# sensor_v6_no_gnd.net
KiCad netlist of a schematic drawn in EAGLE
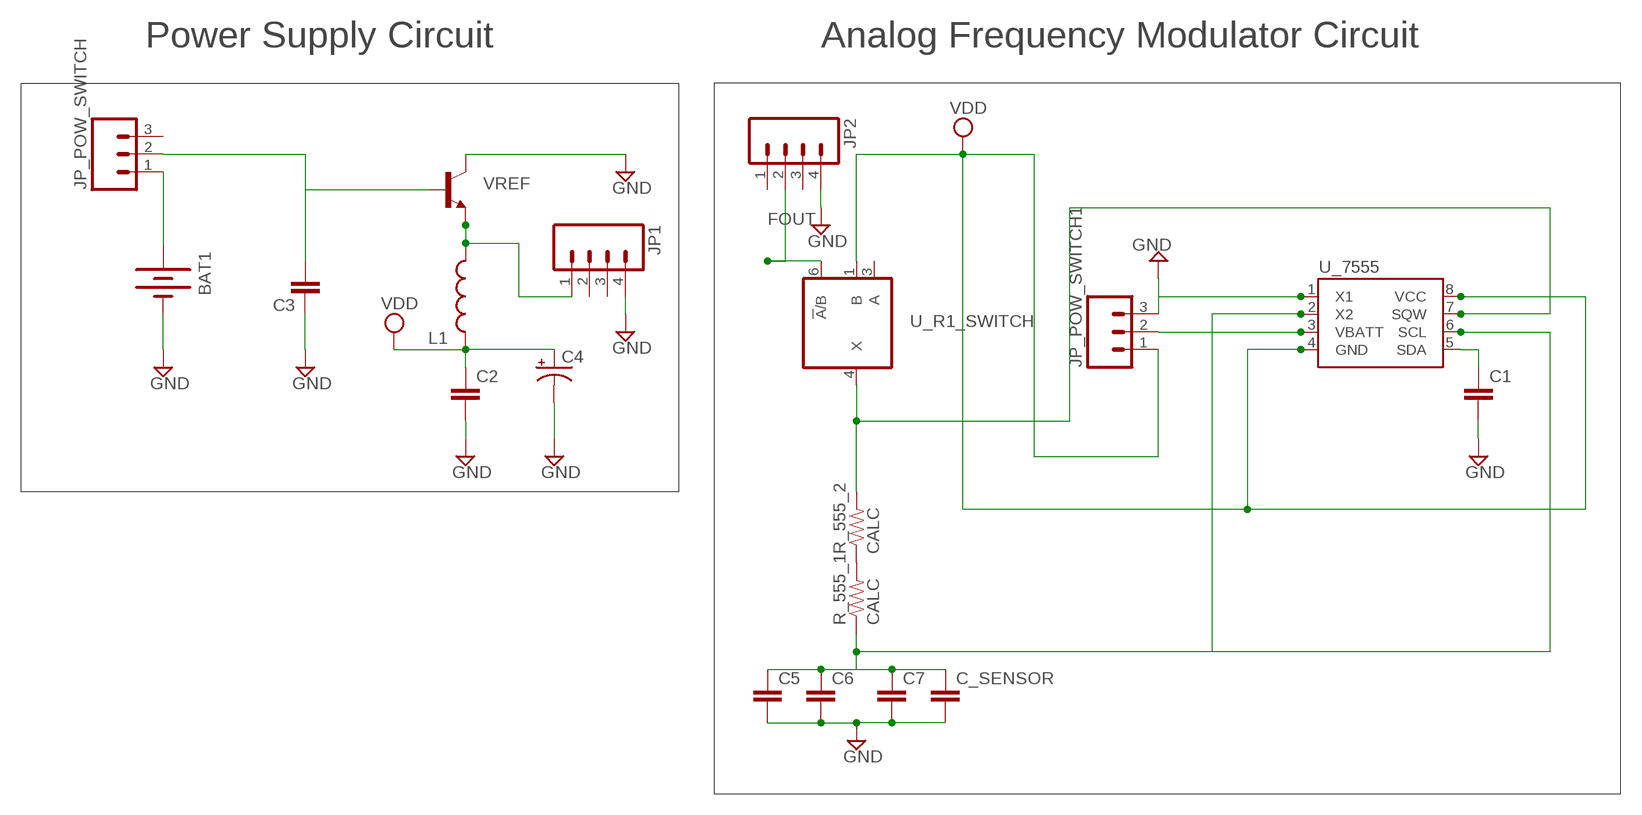
[diagram p0: schematic, sheet 1]

(export (version "E")
  (design (tool "Eeschema 10.0.6"))
  (components
    (comp (ref "BAT1")
      (value "BATTERY20PTH_LAB")
      (footprint "eagle-import:BATTCOM_20MM_PTH")
      (libsource (lib "eagle-import") (part "BATTERY20PTH_LAB"))
    )
    (comp (ref "C1")
      (value "CAP0603-CAP")
      (footprint "eagle-import:0603-CAP")
      (libsource (lib "eagle-import") (part "SparkFun-Capacitors_CAP0603-CAP"))
    )
    (comp (ref "C2")
      (value "CAP0603-CAP")
      (footprint "eagle-import:0603-CAP")
      (libsource (lib "eagle-import") (part "SparkFun-Capacitors_CAP0603-CAP"))
    )
    (comp (ref "C3")
      (value "CAP0603-CAP")
      (footprint "eagle-import:0603-CAP")
      (libsource (lib "eagle-import") (part "SparkFun-Capacitors_CAP0603-CAP"))
    )
    (comp (ref "C4")
      (value "CAP_POL1206")
      (footprint "eagle-import:EIA3216")
      (libsource (lib "eagle-import") (part "CAP_POL1206"))
    )
    (comp (ref "C5")
      (value "CAP0805")
      (footprint "eagle-import:0805")
      (libsource (lib "eagle-import") (part "CAP0805"))
    )
    (comp (ref "C6")
      (value "CAP0805")
      (footprint "eagle-import:0805")
      (libsource (lib "eagle-import") (part "CAP0805"))
    )
    (comp (ref "C7")
      (value "CAP0805")
      (footprint "eagle-import:0805")
      (libsource (lib "eagle-import") (part "CAP0805"))
    )
    (comp (ref "C_SENSOR")
      (value "CAP0805")
      (footprint "eagle-import:0805")
      (libsource (lib "eagle-import") (part "CAP0805"))
    )
    (comp (ref "JP1")
      (value "M04LOCK")
      (footprint "eagle-import:1X04_LOCK")
      (libsource (lib "eagle-import") (part "M04LOCK"))
    )
    (comp (ref "JP2")
      (value "M04LOCK")
      (footprint "eagle-import:1X04_LOCK")
      (libsource (lib "eagle-import") (part "M04LOCK"))
    )
    (comp (ref "JP_POW_SWITCH")
      (value "M03LOCK")
      (footprint "eagle-import:1X03_LOCK")
      (libsource (lib "eagle-import") (part "M03LOCK"))
    )
    (comp (ref "JP_POW_SWITCH1")
      (value "M03LOCK")
      (footprint "eagle-import:1X03_LOCK")
      (libsource (lib "eagle-import") (part "M03LOCK"))
    )
    (comp (ref "L1")
      (value "INDUCTOR0603")
      (footprint "eagle-import:0603")
      (libsource (lib "eagle-import") (part "INDUCTOR0603"))
    )
    (comp (ref "R_555_1")
      (value "CALC")
      (footprint "eagle-import:0805")
      (libsource (lib "eagle-import") (part "RESISTOR0805-RES"))
    )
    (comp (ref "R_555_2")
      (value "CALC")
      (footprint "eagle-import:0805")
      (libsource (lib "eagle-import") (part "RESISTOR0805-RES"))
    )
    (comp (ref "U_7555")
      (value "DS1307SO8")
      (footprint "eagle-import:SO08")
      (libsource (lib "eagle-import") (part "DS1307SO8"))
    )
    (comp (ref "U_R1_SWITCH")
      (value "741G3157DCKR")
      (footprint "eagle-import:DCK_R-PDSO-G6")
      (libsource (lib "eagle-import") (part "741G3157DCKR"))
    )
    (comp (ref "U_VREF")
      (value "TRANSISTOR_NPNSOT23-3")
      (footprint "eagle-import:SOT23-3")
      (libsource (lib "eagle-import") (part "TRANSISTOR_NPNSOT23-3"))
    )
  )
  (nets
    (net (code "1") (name "/FOUT") (class "Default")
      (node (ref "JP2") (pin "2") (pinfunction "2_2") (pintype "passive"))
      (node (ref "JP_POW_SWITCH1") (pin "2") (pinfunction "2_2") (pintype "passive"))
      (node (ref "U_7555") (pin "3") (pinfunction "VBATT_3") (pintype "bidirectional"))
      (node (ref "U_R1_SWITCH") (pin "6") (pinfunction "~{A}/B_6") (pintype "input"))
    )
    (net (code "2") (name "/P2") (class "Default")
      (node (ref "C5") (pin "1") (pinfunction "1_1") (pintype "passive"))
      (node (ref "C6") (pin "1") (pinfunction "1_1") (pintype "passive"))
      (node (ref "C7") (pin "1") (pinfunction "1_1") (pintype "passive"))
      (node (ref "C_SENSOR") (pin "1") (pinfunction "1_1") (pintype "passive"))
      (node (ref "R_555_1") (pin "1") (pinfunction "1_1") (pintype "passive"))
      (node (ref "U_7555") (pin "2") (pinfunction "X2_2") (pintype "bidirectional"))
      (node (ref "U_7555") (pin "6") (pinfunction "SCL_6") (pintype "bidirectional"))
    )
    (net (code "3") (name "GND") (class "Default")
      (node (ref "BAT1") (pin "2") (pinfunction "-_2") (pintype "power_in"))
      (node (ref "C1") (pin "2") (pinfunction "2_2") (pintype "passive"))
      (node (ref "C2") (pin "2") (pinfunction "2_2") (pintype "passive"))
      (node (ref "C3") (pin "1") (pinfunction "1_1") (pintype "passive"))
      (node (ref "C4") (pin "C") (pinfunction "-_C") (pintype "passive"))
      (node (ref "C5") (pin "2") (pinfunction "2_2") (pintype "passive"))
      (node (ref "C6") (pin "2") (pinfunction "2_2") (pintype "passive"))
      (node (ref "C7") (pin "2") (pinfunction "2_2") (pintype "passive"))
      (node (ref "C_SENSOR") (pin "2") (pinfunction "2_2") (pintype "passive"))
      (node (ref "JP1") (pin "4") (pinfunction "4_4") (pintype "passive"))
      (node (ref "JP2") (pin "4") (pinfunction "4_4") (pintype "passive"))
      (node (ref "JP_POW_SWITCH1") (pin "3") (pinfunction "3_3") (pintype "passive"))
      (node (ref "U_7555") (pin "1") (pinfunction "X1_1") (pintype "bidirectional"))
      (node (ref "U_VREF") (pin "3") (pinfunction "C_3") (pintype "passive"))
    )
    (net (code "4") (name "Net-(BAT1-+)") (class "Default")
      (node (ref "BAT1") (pin "1") (pinfunction "+_1") (pintype "power_in"))
      (node (ref "JP_POW_SWITCH") (pin "1") (pinfunction "1_1") (pintype "passive"))
    )
    (net (code "5") (name "Net-(R_555_1-Pad2)") (class "Default")
      (node (ref "R_555_1") (pin "2") (pinfunction "2_2") (pintype "passive"))
      (node (ref "R_555_2") (pin "1") (pinfunction "1_1") (pintype "passive"))
    )
    (net (code "6") (name "Net-(U_7555-SDA)") (class "Default")
      (node (ref "C1") (pin "1") (pinfunction "1_1") (pintype "passive"))
      (node (ref "U_7555") (pin "5") (pinfunction "SDA_5") (pintype "bidirectional"))
    )
    (net (code "7") (name "Net-(U_7555-SQW)") (class "Default")
      (node (ref "R_555_2") (pin "2") (pinfunction "2_2") (pintype "passive"))
      (node (ref "U_7555") (pin "7") (pinfunction "SQW_7") (pintype "bidirectional"))
      (node (ref "U_R1_SWITCH") (pin "4") (pinfunction "X_4") (pintype "bidirectional"))
    )
    (net (code "8") (name "Net-(U_VREF-B)") (class "Default")
      (node (ref "C3") (pin "2") (pinfunction "2_2") (pintype "passive"))
      (node (ref "JP_POW_SWITCH") (pin "2") (pinfunction "2_2") (pintype "passive"))
      (node (ref "U_VREF") (pin "1") (pinfunction "B_1") (pintype "passive"))
    )
    (net (code "9") (name "Net-(U_VREF-E)") (class "Default")
      (node (ref "JP1") (pin "1") (pinfunction "1_1") (pintype "passive"))
      (node (ref "L1") (pin "2") (pinfunction "2_2") (pintype "passive"))
      (node (ref "U_VREF") (pin "2") (pinfunction "E_2") (pintype "passive"))
    )
    (net (code "10") (name "VDD") (class "Default")
      (node (ref "C2") (pin "1") (pinfunction "1_1") (pintype "passive"))
      (node (ref "C4") (pin "A") (pinfunction "+_A") (pintype "passive"))
      (node (ref "JP_POW_SWITCH1") (pin "1") (pinfunction "1_1") (pintype "passive"))
      (node (ref "L1") (pin "1") (pinfunction "1_1") (pintype "passive"))
      (node (ref "U_7555") (pin "4") (pinfunction "GND_4") (pintype "bidirectional"))
      (node (ref "U_7555") (pin "8") (pinfunction "VCC_8") (pintype "bidirectional"))
      (node (ref "U_R1_SWITCH") (pin "1") (pinfunction "B_1") (pintype "bidirectional"))
    )
    (net (code "11") (name "unconnected-(JP1-Pad2)") (class "Default")
      (node (ref "JP1") (pin "2") (pinfunction "2_2") (pintype "passive"))
    )
    (net (code "12") (name "unconnected-(JP1-Pad3)") (class "Default")
      (node (ref "JP1") (pin "3") (pinfunction "3_3") (pintype "passive"))
    )
    (net (code "13") (name "unconnected-(JP2-Pad1)") (class "Default")
      (node (ref "JP2") (pin "1") (pinfunction "1_1") (pintype "passive"))
    )
    (net (code "14") (name "unconnected-(JP2-Pad3)") (class "Default")
      (node (ref "JP2") (pin "3") (pinfunction "3_3") (pintype "passive"))
    )
    (net (code "15") (name "unconnected-(JP_POW_SWITCH-Pad3)") (class "Default")
      (node (ref "JP_POW_SWITCH") (pin "3") (pinfunction "3_3") (pintype "passive"))
    )
    (net (code "16") (name "unconnected-(U_R1_SWITCHA-A-Pad3)") (class "Default")
      (node (ref "U_R1_SWITCH") (pin "3") (pinfunction "A_3") (pintype "bidirectional"))
    )
  )
)
